# Modul_I2C.net
KiCad netlist of a schematic drawn in EAGLE
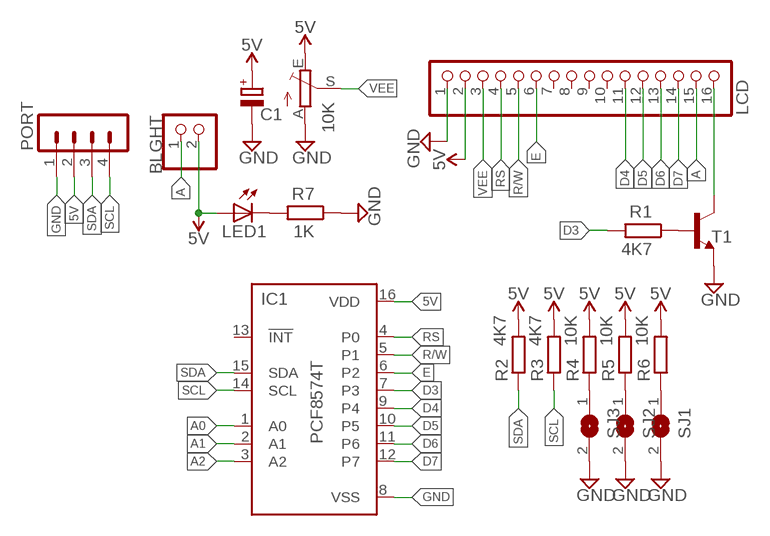
[diagram p0: schematic, sheet 1]

(export (version "E")
  (design (tool "Eeschema 10.0.6"))
  (components
    (comp (ref "10K")
      (value "TRIM_EU-CT6")
      (footprint "eagle-import:CT6")
      (libsource (lib "eagle-import") (part "TRIM_EU-CT6"))
    )
    (comp (ref "BLGHT")
      (value "PINHD-1X2")
      (footprint "eagle-import:1X02")
      (libsource (lib "eagle-import") (part "PINHD-1X2"))
    )
    (comp (ref "C1")
      (value "CPOL-EUE2.5-5")
      (footprint "eagle-import:E2,5-5")
      (libsource (lib "eagle-import") (part "CPOL-EUE2.5-5"))
    )
    (comp (ref "IC1")
      (value "PCF8574T")
      (footprint "eagle-import:SO16W")
      (fields (field (name "MPN") "PCF8574T/3,512"))
      (libsource (lib "eagle-import") (part "PCF8574T"))
    )
    (comp (ref "LCD")
      (value "PINHD-1X16")
      (footprint "eagle-import:1X16")
      (libsource (lib "eagle-import") (part "PINHD-1X16"))
    )
    (comp (ref "LED1")
      (value "LED3MM")
      (footprint "eagle-import:LED3MM")
      (libsource (lib "eagle-import") (part "LED3MM"))
    )
    (comp (ref "PORT")
      (value "MA04-1")
      (footprint "eagle-import:MA04-1")
      (libsource (lib "eagle-import") (part "MA04-1"))
    )
    (comp (ref "R1")
      (value "4K7")
      (footprint "eagle-import:R0805")
      (libsource (lib "eagle-import") (part "R-EU_R0805"))
    )
    (comp (ref "R2")
      (value "4K7")
      (footprint "eagle-import:R0805")
      (libsource (lib "eagle-import") (part "R-EU_R0805"))
    )
    (comp (ref "R3")
      (value "4K7")
      (footprint "eagle-import:R0805")
      (libsource (lib "eagle-import") (part "R-EU_R0805"))
    )
    (comp (ref "R4")
      (value "10K")
      (footprint "eagle-import:R0805")
      (libsource (lib "eagle-import") (part "R-EU_R0805"))
    )
    (comp (ref "R5")
      (value "10K")
      (footprint "eagle-import:R0805")
      (libsource (lib "eagle-import") (part "R-EU_R0805"))
    )
    (comp (ref "R6")
      (value "10K")
      (footprint "eagle-import:R0805")
      (libsource (lib "eagle-import") (part "R-EU_R0805"))
    )
    (comp (ref "R7")
      (value "1K")
      (footprint "eagle-import:R0805")
      (libsource (lib "eagle-import") (part "R-EU_R0805"))
    )
    (comp (ref "SJ1") (value "SJ") (footprint "eagle-import:SJ") (libsource (lib "eagle-import") (part "SJ")))
    (comp (ref "SJ2") (value "SJ") (footprint "eagle-import:SJ") (libsource (lib "eagle-import") (part "SJ")))
    (comp (ref "SJ3") (value "SJ") (footprint "eagle-import:SJ") (libsource (lib "eagle-import") (part "SJ")))
    (comp (ref "T1")
      (value "MMBT918LT1-NPN-SOT23-BEC")
      (footprint "eagle-import:SOT23-BEC")
      (libsource (lib "eagle-import") (part "-NPN-SOT23-BECMMBT918LT1"))
    )
  )
  (nets
    (net (code "1") (name "5V") (class "Default")
      (node (ref "10K") (pin "E") (pinfunction "E_E") (pintype "passive"))
      (node (ref "BLGHT") (pin "2") (pinfunction "2_2") (pintype "passive"))
      (node (ref "C1") (pin "+") (pinfunction "+_+") (pintype "passive"))
      (node (ref "IC1") (pin "16") (pinfunction "VDD_16") (pintype "power_in"))
      (node (ref "LCD") (pin "2") (pinfunction "2_2") (pintype "passive"))
      (node (ref "LED1") (pin "A") (pinfunction "A_A") (pintype "passive"))
      (node (ref "PORT") (pin "2") (pinfunction "2_2") (pintype "passive"))
      (node (ref "R2") (pin "2") (pinfunction "2_2") (pintype "passive"))
      (node (ref "R3") (pin "2") (pinfunction "2_2") (pintype "passive"))
      (node (ref "R4") (pin "2") (pinfunction "2_2") (pintype "passive"))
      (node (ref "R5") (pin "2") (pinfunction "2_2") (pintype "passive"))
      (node (ref "R6") (pin "2") (pinfunction "2_2") (pintype "passive"))
    )
    (net (code "2") (name "A") (class "Default")
      (node (ref "BLGHT") (pin "1") (pinfunction "1_1") (pintype "passive"))
      (node (ref "LCD") (pin "15") (pinfunction "15_15") (pintype "passive"))
    )
    (net (code "3") (name "A0") (class "Default")
      (node (ref "IC1") (pin "1") (pinfunction "A0_1") (pintype "input"))
    )
    (net (code "4") (name "A1") (class "Default")
      (node (ref "IC1") (pin "2") (pinfunction "A1_2") (pintype "input"))
    )
    (net (code "5") (name "A2") (class "Default")
      (node (ref "IC1") (pin "3") (pinfunction "A2_3") (pintype "input"))
    )
    (net (code "6") (name "D3") (class "Default")
      (node (ref "IC1") (pin "7") (pinfunction "P3_7") (pintype "bidirectional"))
      (node (ref "R1") (pin "2") (pinfunction "2_2") (pintype "passive"))
    )
    (net (code "7") (name "D4") (class "Default")
      (node (ref "IC1") (pin "9") (pinfunction "P4_9") (pintype "bidirectional"))
      (node (ref "LCD") (pin "11") (pinfunction "11_11") (pintype "passive"))
    )
    (net (code "8") (name "D5") (class "Default")
      (node (ref "IC1") (pin "10") (pinfunction "P5_10") (pintype "bidirectional"))
      (node (ref "LCD") (pin "12") (pinfunction "12_12") (pintype "passive"))
    )
    (net (code "9") (name "D6") (class "Default")
      (node (ref "IC1") (pin "11") (pinfunction "P6_11") (pintype "bidirectional"))
      (node (ref "LCD") (pin "13") (pinfunction "13_13") (pintype "passive"))
    )
    (net (code "10") (name "D7") (class "Default")
      (node (ref "IC1") (pin "12") (pinfunction "P7_12") (pintype "bidirectional"))
      (node (ref "LCD") (pin "14") (pinfunction "14_14") (pintype "passive"))
    )
    (net (code "11") (name "E") (class "Default")
      (node (ref "IC1") (pin "6") (pinfunction "P2_6") (pintype "bidirectional"))
      (node (ref "LCD") (pin "6") (pinfunction "6_6") (pintype "passive"))
    )
    (net (code "12") (name "GND") (class "Default")
      (node (ref "10K") (pin "A") (pinfunction "A_A") (pintype "passive"))
      (node (ref "C1") (pin "-") (pinfunction "-_-") (pintype "passive"))
      (node (ref "IC1") (pin "8") (pinfunction "VSS_8") (pintype "power_in"))
      (node (ref "LCD") (pin "1") (pinfunction "1_1") (pintype "passive"))
      (node (ref "PORT") (pin "1") (pinfunction "1_1") (pintype "passive"))
      (node (ref "R7") (pin "1") (pinfunction "1_1") (pintype "passive"))
      (node (ref "SJ1") (pin "2") (pinfunction "2_2") (pintype "passive"))
      (node (ref "SJ2") (pin "2") (pinfunction "2_2") (pintype "passive"))
      (node (ref "SJ3") (pin "2") (pinfunction "2_2") (pintype "passive"))
      (node (ref "T1") (pin "E") (pinfunction "E_E") (pintype "passive"))
    )
    (net (code "13") (name "Net-(LCD-Pad16)") (class "Default")
      (node (ref "LCD") (pin "16") (pinfunction "16_16") (pintype "passive"))
      (node (ref "T1") (pin "C") (pinfunction "C_C") (pintype "passive"))
    )
    (net (code "14") (name "Net-(LED1-C)") (class "Default")
      (node (ref "LED1") (pin "K") (pinfunction "C_K") (pintype "passive"))
      (node (ref "R7") (pin "2") (pinfunction "2_2") (pintype "passive"))
    )
    (net (code "15") (name "Net-(R1-Pad1)") (class "Default")
      (node (ref "R1") (pin "1") (pinfunction "1_1") (pintype "passive"))
      (node (ref "T1") (pin "B") (pinfunction "B_B") (pintype "passive"))
    )
    (net (code "16") (name "Net-(R4-Pad1)") (class "Default")
      (node (ref "R4") (pin "1") (pinfunction "1_1") (pintype "passive"))
      (node (ref "SJ3") (pin "1") (pinfunction "1_1") (pintype "passive"))
    )
    (net (code "17") (name "Net-(R5-Pad1)") (class "Default")
      (node (ref "R5") (pin "1") (pinfunction "1_1") (pintype "passive"))
      (node (ref "SJ2") (pin "1") (pinfunction "1_1") (pintype "passive"))
    )
    (net (code "18") (name "Net-(R6-Pad1)") (class "Default")
      (node (ref "R6") (pin "1") (pinfunction "1_1") (pintype "passive"))
      (node (ref "SJ1") (pin "1") (pinfunction "1_1") (pintype "passive"))
    )
    (net (code "19") (name "RS") (class "Default")
      (node (ref "IC1") (pin "4") (pinfunction "P0_4") (pintype "bidirectional"))
      (node (ref "LCD") (pin "4") (pinfunction "4_4") (pintype "passive"))
    )
    (net (code "20") (name "R{slash}W") (class "Default")
      (node (ref "IC1") (pin "5") (pinfunction "P1_5") (pintype "bidirectional"))
      (node (ref "LCD") (pin "5") (pinfunction "5_5") (pintype "passive"))
    )
    (net (code "21") (name "SCL") (class "Default")
      (node (ref "IC1") (pin "14") (pinfunction "SCL_14") (pintype "input"))
      (node (ref "PORT") (pin "4") (pinfunction "4_4") (pintype "passive"))
      (node (ref "R3") (pin "1") (pinfunction "1_1") (pintype "passive"))
    )
    (net (code "22") (name "SDA") (class "Default")
      (node (ref "IC1") (pin "15") (pinfunction "SDA_15") (pintype "bidirectional"))
      (node (ref "PORT") (pin "3") (pinfunction "3_3") (pintype "passive"))
      (node (ref "R2") (pin "1") (pinfunction "1_1") (pintype "passive"))
    )
    (net (code "23") (name "VEE") (class "Default")
      (node (ref "10K") (pin "S") (pinfunction "S_S") (pintype "passive"))
      (node (ref "LCD") (pin "3") (pinfunction "3_3") (pintype "passive"))
    )
    (net (code "24") (name "unconnected-(IC1-~{INT}-Pad13)") (class "Default")
      (node (ref "IC1") (pin "13") (pinfunction "~{INT}_13") (pintype "output"))
    )
    (net (code "25") (name "unconnected-(LCD-Pad7)") (class "Default")
      (node (ref "LCD") (pin "7") (pinfunction "7_7") (pintype "passive"))
    )
    (net (code "26") (name "unconnected-(LCD-Pad8)") (class "Default")
      (node (ref "LCD") (pin "8") (pinfunction "8_8") (pintype "passive"))
    )
    (net (code "27") (name "unconnected-(LCD-Pad9)") (class "Default")
      (node (ref "LCD") (pin "9") (pinfunction "9_9") (pintype "passive"))
    )
    (net (code "28") (name "unconnected-(LCD-Pad10)") (class "Default")
      (node (ref "LCD") (pin "10") (pinfunction "10_10") (pintype "passive"))
    )
  )
)
